# easy_eda_pro_file.net
KiCad netlist of a schematic drawn in EasyEDA Pro
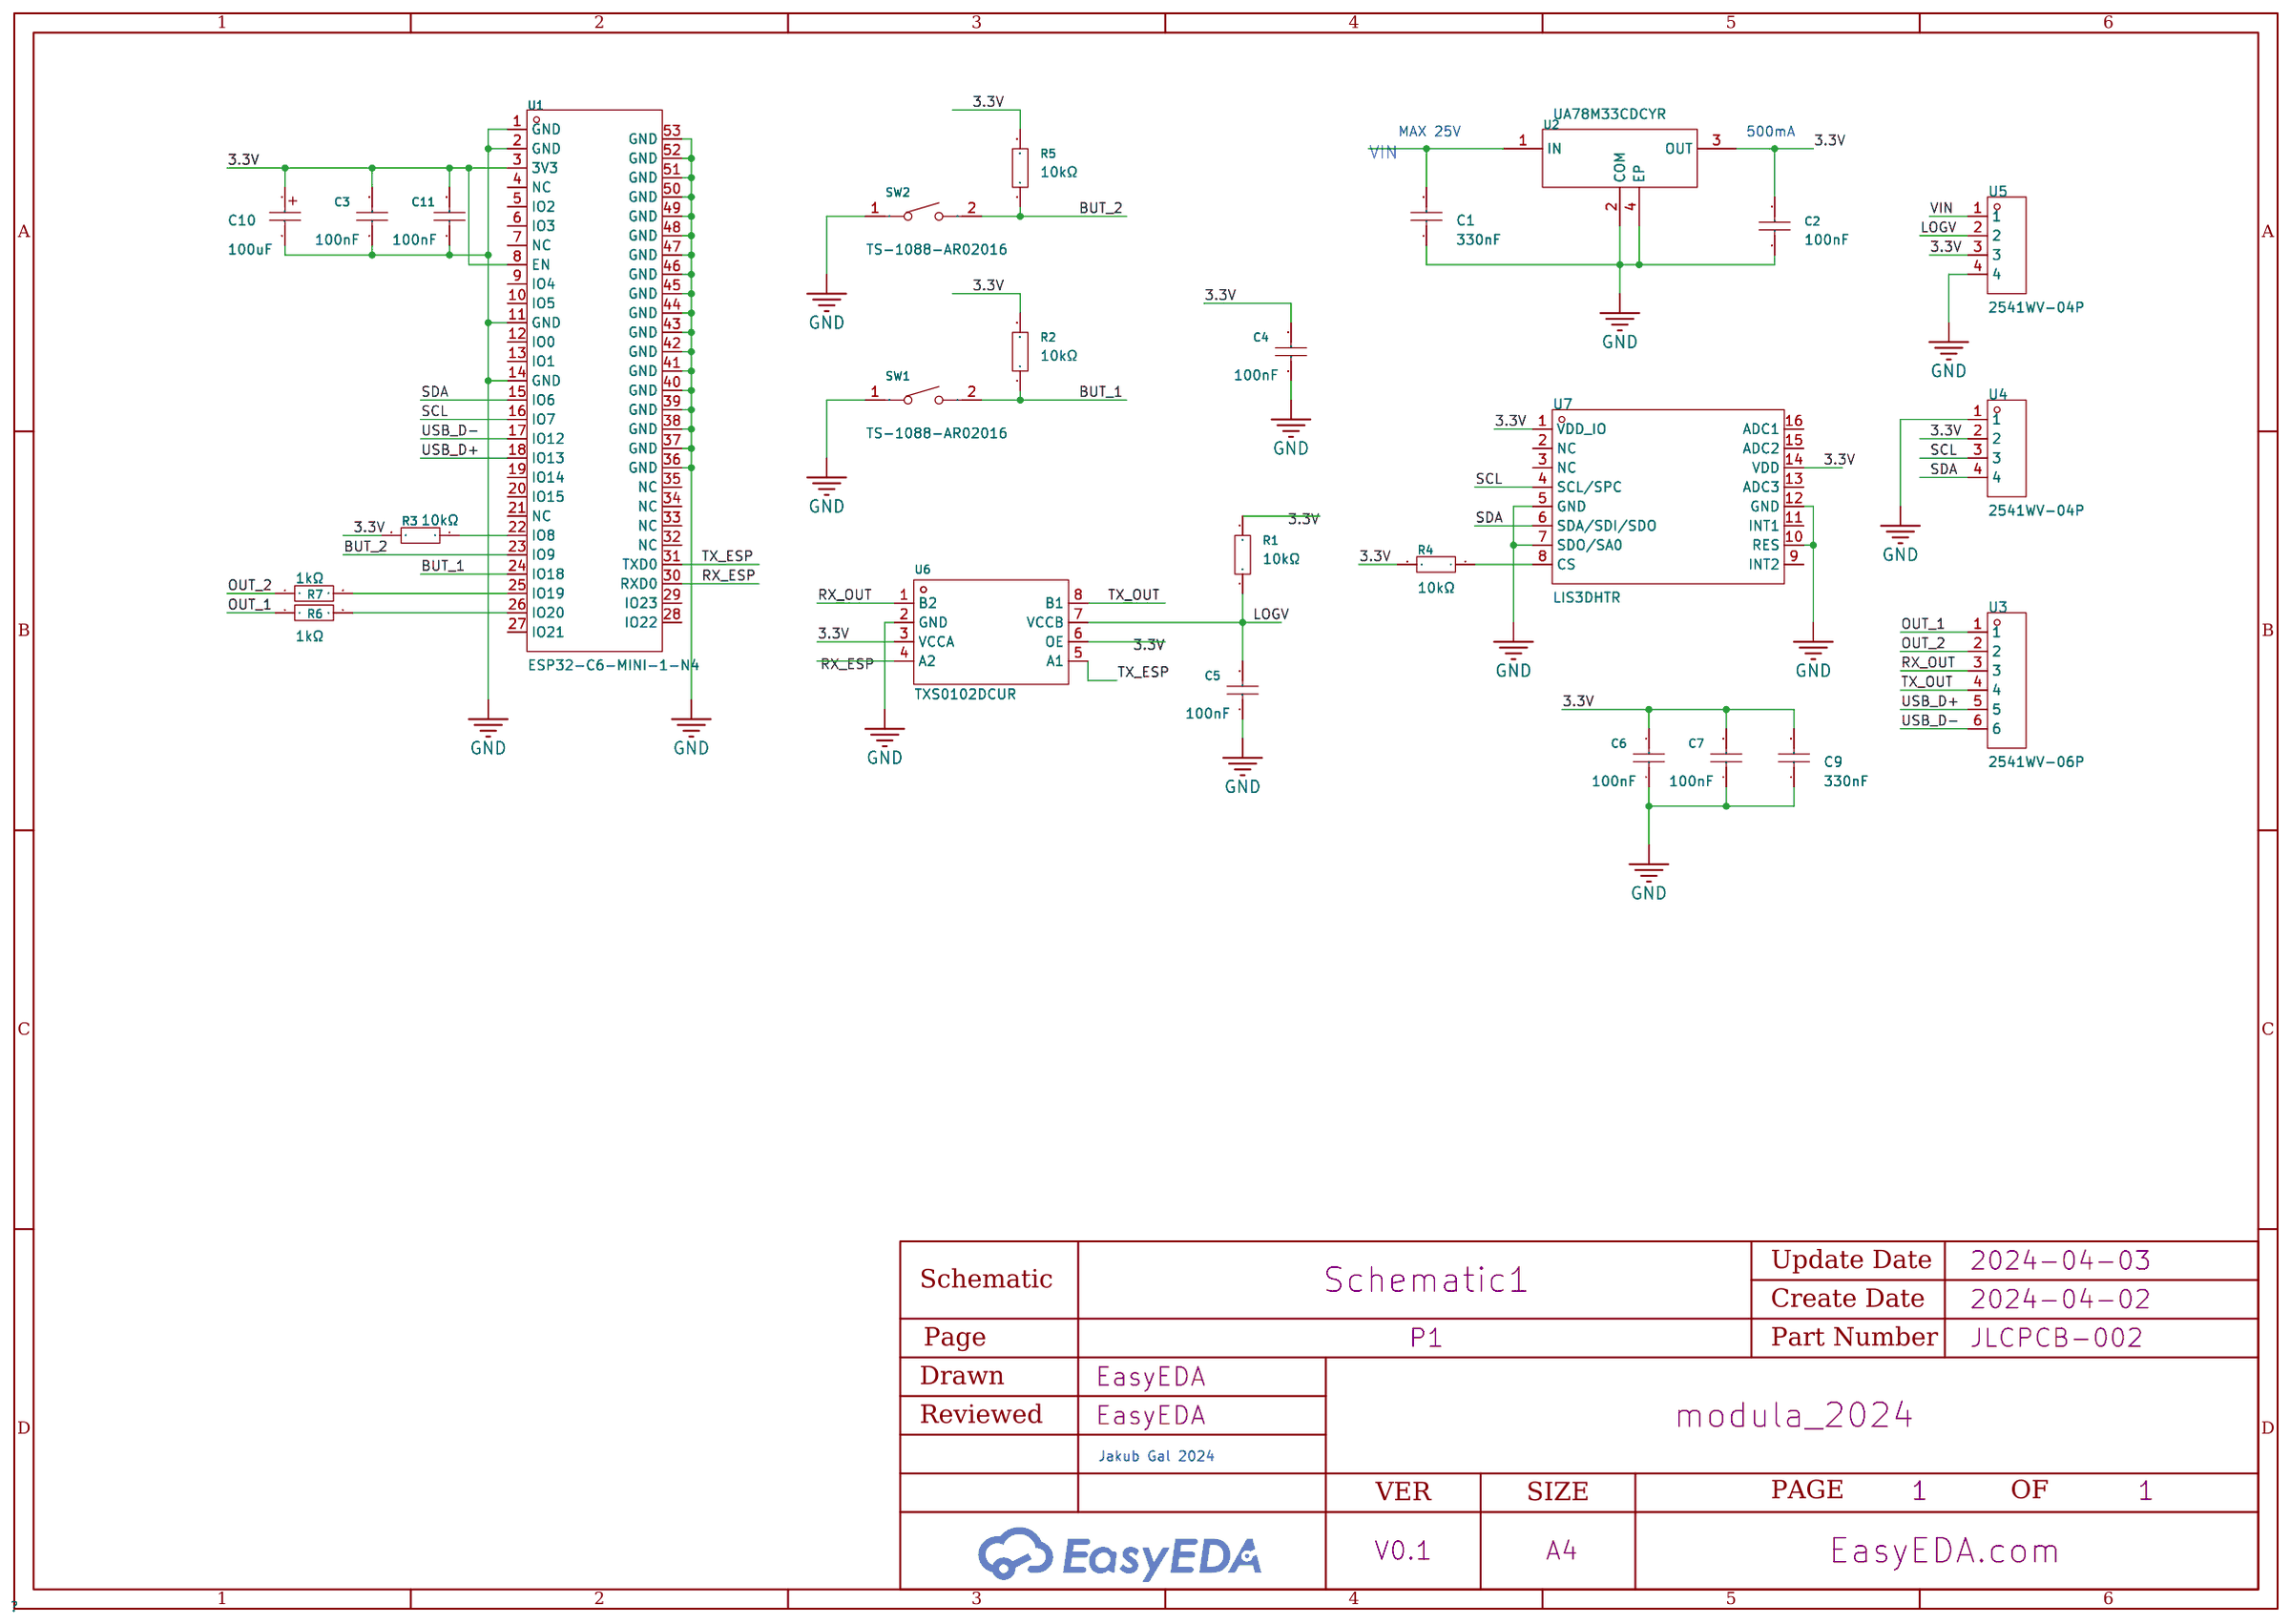
[diagram p0: schematic sheet]

(export (version "E")
  (design (tool "Eeschema 10.0.6"))
  (components
    (comp (ref "C1")
      (value "330nF")
      (footprint "easyedapro:C0805")
      (fields (field (name "Manufacturer Part") "0805B334K500NT") (field (name "Manufacturer") "FH(风华)"))
      (libsource (lib "easyedapro") (part "0805B334K500NT"))
    )
    (comp (ref "C2")
      (value "100nF")
      (footprint "easyedapro:C0603")
      (fields (field (name "Manufacturer Part") "0603B104K500NT") (field (name "Manufacturer") "FH(风华)"))
      (libsource (lib "easyedapro") (part "0603B104K500NT"))
    )
    (comp (ref "C3")
      (value "100nF")
      (footprint "easyedapro:C0603")
      (fields (field (name "Manufacturer Part") "0603B104K500NT") (field (name "Manufacturer") "FH(风华)"))
      (libsource (lib "easyedapro") (part "0603B104K500NT"))
    )
    (comp (ref "C4")
      (value "100nF")
      (footprint "easyedapro:C0603")
      (fields (field (name "Manufacturer Part") "0603B104K500NT") (field (name "Manufacturer") "FH(风华)"))
      (libsource (lib "easyedapro") (part "0603B104K500NT"))
    )
    (comp (ref "C5")
      (value "100nF")
      (footprint "easyedapro:C0603")
      (fields (field (name "Manufacturer Part") "0603B104K500NT") (field (name "Manufacturer") "FH(风华)"))
      (libsource (lib "easyedapro") (part "0603B104K500NT"))
    )
    (comp (ref "C6")
      (value "100nF")
      (footprint "easyedapro:C0603")
      (fields (field (name "Manufacturer Part") "0603B104K500NT") (field (name "Manufacturer") "FH(风华)"))
      (libsource (lib "easyedapro") (part "0603B104K500NT"))
    )
    (comp (ref "C7")
      (value "100nF")
      (footprint "easyedapro:C0603")
      (fields (field (name "Manufacturer Part") "0603B104K500NT") (field (name "Manufacturer") "FH(风华)"))
      (libsource (lib "easyedapro") (part "0603B104K500NT"))
    )
    (comp (ref "C9")
      (value "330nF")
      (footprint "easyedapro:C0805")
      (fields (field (name "Manufacturer Part") "0805B334K500NT") (field (name "Manufacturer") "FH(风华)"))
      (libsource (lib "easyedapro") (part "0805B334K500NT"))
    )
    (comp (ref "C10")
      (value "100uF")
      (footprint "easyedapro:CAP-SMD_L3.5-W2.8-R-RD")
      (fields
        (field (name "Manufacturer Part") "CA45-B-6.3V-100uF-K")
        (field (name "Manufacturer") "CEC(振华新云)")
      )
      (libsource (lib "easyedapro") (part "CA45-B-6.3V-100UF-K"))
    )
    (comp (ref "C11")
      (value "100nF")
      (footprint "easyedapro:C0603")
      (fields (field (name "Manufacturer Part") "0603B104K500NT") (field (name "Manufacturer") "FH(风华)"))
      (libsource (lib "easyedapro") (part "0603B104K500NT"))
    )
    (comp (ref "R1")
      (value "10kΩ")
      (footprint "easyedapro:R0603")
      (fields
        (field (name "Manufacturer Part") "0603WAF1002T5E")
        (field (name "Manufacturer") "UNI-ROYAL(厚声)")
      )
      (libsource (lib "easyedapro") (part "0603WAF1002T5E"))
    )
    (comp (ref "R2")
      (value "10kΩ")
      (footprint "easyedapro:R0603")
      (fields
        (field (name "Manufacturer Part") "0603WAF1002T5E")
        (field (name "Manufacturer") "UNI-ROYAL(厚声)")
      )
      (libsource (lib "easyedapro") (part "0603WAF1002T5E"))
    )
    (comp (ref "R3")
      (value "10kΩ")
      (footprint "easyedapro:R0603")
      (fields
        (field (name "Manufacturer Part") "0603WAF1002T5E")
        (field (name "Manufacturer") "UNI-ROYAL(厚声)")
      )
      (libsource (lib "easyedapro") (part "0603WAF1002T5E"))
    )
    (comp (ref "R4")
      (value "10kΩ")
      (footprint "easyedapro:R0603")
      (fields
        (field (name "Manufacturer Part") "0603WAF1002T5E")
        (field (name "Manufacturer") "UNI-ROYAL(厚声)")
      )
      (libsource (lib "easyedapro") (part "0603WAF1002T5E"))
    )
    (comp (ref "R5")
      (value "10kΩ")
      (footprint "easyedapro:R0603")
      (fields
        (field (name "Manufacturer Part") "0603WAF1002T5E")
        (field (name "Manufacturer") "UNI-ROYAL(厚声)")
      )
      (libsource (lib "easyedapro") (part "0603WAF1002T5E"))
    )
    (comp (ref "R6")
      (value "1kΩ")
      (footprint "easyedapro:R0603")
      (fields
        (field (name "Manufacturer Part") "0603WAJ0102T5E")
        (field (name "Manufacturer") "UNI-ROYAL(厚声)")
      )
      (libsource (lib "easyedapro") (part "0603WAJ0102T5E"))
    )
    (comp (ref "R7")
      (value "1kΩ")
      (footprint "easyedapro:R0603")
      (fields
        (field (name "Manufacturer Part") "0603WAJ0102T5E")
        (field (name "Manufacturer") "UNI-ROYAL(厚声)")
      )
      (libsource (lib "easyedapro") (part "0603WAJ0102T5E"))
    )
    (comp (ref "SW1")
      (value "TS-1088-AR02016")
      (footprint "easyedapro:SW-SMD_L3.9-W3.0-P4.45")
      (fields (field (name "Manufacturer") "XUNPU(讯普)"))
      (libsource (lib "easyedapro") (part "TS-1088-AR02016"))
    )
    (comp (ref "SW2")
      (value "TS-1088-AR02016")
      (footprint "easyedapro:SW-SMD_L3.9-W3.0-P4.45")
      (fields (field (name "Manufacturer") "XUNPU(讯普)"))
      (libsource (lib "easyedapro") (part "TS-1088-AR02016"))
    )
    (comp (ref "U1")
      (value "ESP32-C6-MINI-1-N4")
      (footprint "easyedapro:WIFIM-SMD_61P-L16.6-W13.2-P0.80-ESP32-C6-MINI-1-N4")
      (fields (field (name "Manufacturer") "ESPRESSIF(乐鑫)"))
      (libsource (lib "easyedapro") (part "ESP32-C6-MINI-1-N4"))
    )
    (comp (ref "U2")
      (value "UA78M33CDCYR")
      (footprint "easyedapro:SOT-223_L6.5-W3.5-P2.30-LS7.0-BR")
      (fields (field (name "Manufacturer") "TI(德州仪器)"))
      (libsource (lib "easyedapro") (part "UA78M33CDCYR"))
    )
    (comp (ref "U3")
      (value "2541WV-06P")
      (footprint "easyedapro:HDR-TH_6P-P2.54-V-M")
      (fields (field (name "Manufacturer") "HanElectricity(瀚源)"))
      (libsource (lib "easyedapro") (part "2541WV-06P"))
    )
    (comp (ref "U4")
      (value "2541WV-04P")
      (footprint "easyedapro:HDR-TH_4P-P2.54-V-M-1")
      (fields (field (name "Manufacturer") "HanElectricity(瀚源)"))
      (libsource (lib "easyedapro") (part "2541WV-04P"))
    )
    (comp (ref "U5")
      (value "2541WV-04P")
      (footprint "easyedapro:HDR-TH_4P-P2.54-V-M-1")
      (fields (field (name "Manufacturer") "HanElectricity(瀚源)"))
      (libsource (lib "easyedapro") (part "2541WV-04P"))
    )
    (comp (ref "U6")
      (value "TXS0102DCUR")
      (footprint "easyedapro:VSON8_L2.0-W2.3-P0.50-LS3.1-BL")
      (fields (field (name "Manufacturer") "TI(德州仪器)"))
      (libsource (lib "easyedapro") (part "TXS0102DCUR"))
    )
    (comp (ref "U7")
      (value "LIS3DHTR")
      (footprint "easyedapro:LGA-16_L3.0-W3.0-P0.50-TL")
      (fields (field (name "Manufacturer") "ST(意法半导体)"))
      (libsource (lib "easyedapro") (part "LIS3DHTR_C15134"))
    )
  )
  (nets
    (net (code "1") (name "/3.3V") (class "Default")
      (node (ref "C10") (pin "1") (pinfunction "1_1") (pintype "input"))
      (node (ref "C11") (pin "2") (pinfunction "2_2") (pintype "input"))
      (node (ref "C2") (pin "2") (pinfunction "2_2") (pintype "input"))
      (node (ref "C3") (pin "2") (pinfunction "2_2") (pintype "input"))
      (node (ref "C4") (pin "2") (pinfunction "2_2") (pintype "input"))
      (node (ref "C6") (pin "2") (pinfunction "2_2") (pintype "input"))
      (node (ref "C7") (pin "2") (pinfunction "2_2") (pintype "input"))
      (node (ref "C9") (pin "2") (pinfunction "2_2") (pintype "input"))
      (node (ref "R1") (pin "2") (pinfunction "2_2") (pintype "input"))
      (node (ref "R2") (pin "2") (pinfunction "2_2") (pintype "input"))
      (node (ref "R3") (pin "2") (pinfunction "2_2") (pintype "input"))
      (node (ref "R4") (pin "2") (pinfunction "2_2") (pintype "input"))
      (node (ref "R5") (pin "2") (pinfunction "2_2") (pintype "input"))
      (node (ref "U1") (pin "3") (pinfunction "3V3_3") (pintype "input"))
      (node (ref "U1") (pin "8") (pinfunction "EN_8") (pintype "input"))
      (node (ref "U2") (pin "3") (pinfunction "OUT_3") (pintype "input"))
      (node (ref "U4") (pin "2") (pinfunction "2_2") (pintype "input"))
      (node (ref "U5") (pin "3") (pinfunction "3_3") (pintype "input"))
      (node (ref "U6") (pin "3") (pinfunction "VCCA_3") (pintype "input"))
      (node (ref "U6") (pin "6") (pinfunction "OE_6") (pintype "input"))
      (node (ref "U7") (pin "1") (pinfunction "VDD_IO_1") (pintype "unspecified"))
      (node (ref "U7") (pin "14") (pinfunction "VDD_14") (pintype "unspecified"))
    )
    (net (code "2") (name "/BUT_1") (class "Default")
      (node (ref "R2") (pin "1") (pinfunction "1_1") (pintype "input"))
      (node (ref "SW1") (pin "2") (pinfunction "2_2") (pintype "input"))
      (node (ref "U1") (pin "24") (pinfunction "IO18_24") (pintype "input"))
    )
    (net (code "3") (name "/BUT_2") (class "Default")
      (node (ref "R5") (pin "1") (pinfunction "1_1") (pintype "input"))
      (node (ref "SW2") (pin "2") (pinfunction "2_2") (pintype "input"))
      (node (ref "U1") (pin "23") (pinfunction "IO9_23") (pintype "input"))
    )
    (net (code "4") (name "/LOGV") (class "Default")
      (node (ref "C5") (pin "2") (pinfunction "2_2") (pintype "input"))
      (node (ref "R1") (pin "1") (pinfunction "1_1") (pintype "input"))
      (node (ref "U5") (pin "2") (pinfunction "2_2") (pintype "input"))
      (node (ref "U6") (pin "7") (pinfunction "VCCB_7") (pintype "input"))
    )
    (net (code "5") (name "/OUT_1") (class "Default")
      (node (ref "R6") (pin "1") (pinfunction "1_1") (pintype "input"))
      (node (ref "U3") (pin "1") (pinfunction "1_1") (pintype "unspecified"))
    )
    (net (code "6") (name "/OUT_2") (class "Default")
      (node (ref "R7") (pin "1") (pinfunction "1_1") (pintype "input"))
      (node (ref "U3") (pin "2") (pinfunction "2_2") (pintype "unspecified"))
    )
    (net (code "7") (name "/RX_ESP") (class "Default")
      (node (ref "U1") (pin "30") (pinfunction "RXD0_30") (pintype "input"))
      (node (ref "U6") (pin "4") (pinfunction "A2_4") (pintype "input"))
    )
    (net (code "8") (name "/RX_OUT") (class "Default")
      (node (ref "U3") (pin "3") (pinfunction "3_3") (pintype "unspecified"))
      (node (ref "U6") (pin "1") (pinfunction "B2_1") (pintype "input"))
    )
    (net (code "9") (name "/SCL") (class "Default")
      (node (ref "U1") (pin "16") (pinfunction "IO7_16") (pintype "input"))
      (node (ref "U4") (pin "3") (pinfunction "3_3") (pintype "input"))
      (node (ref "U7") (pin "4") (pinfunction "SCL/SPC_4") (pintype "unspecified"))
    )
    (net (code "10") (name "/SDA") (class "Default")
      (node (ref "U1") (pin "15") (pinfunction "IO6_15") (pintype "input"))
      (node (ref "U4") (pin "4") (pinfunction "4_4") (pintype "input"))
      (node (ref "U7") (pin "6") (pinfunction "SDA/SDI/SDO_6") (pintype "unspecified"))
    )
    (net (code "11") (name "/TX_ESP") (class "Default")
      (node (ref "U1") (pin "31") (pinfunction "TXD0_31") (pintype "input"))
      (node (ref "U6") (pin "5") (pinfunction "A1_5") (pintype "input"))
    )
    (net (code "12") (name "/TX_OUT") (class "Default")
      (node (ref "U3") (pin "4") (pinfunction "4_4") (pintype "unspecified"))
      (node (ref "U6") (pin "8") (pinfunction "B1_8") (pintype "input"))
    )
    (net (code "13") (name "/USB_D+") (class "Default")
      (node (ref "U1") (pin "18") (pinfunction "IO13_18") (pintype "input"))
      (node (ref "U3") (pin "5") (pinfunction "5_5") (pintype "unspecified"))
    )
    (net (code "14") (name "/USB_D-") (class "Default")
      (node (ref "U1") (pin "17") (pinfunction "IO12_17") (pintype "input"))
      (node (ref "U3") (pin "6") (pinfunction "6_6") (pintype "unspecified"))
    )
    (net (code "15") (name "/VIN") (class "Default")
      (node (ref "C1") (pin "2") (pinfunction "2_2") (pintype "input"))
      (node (ref "U2") (pin "1") (pinfunction "IN_1") (pintype "input"))
      (node (ref "U5") (pin "1") (pinfunction "1_1") (pintype "input"))
    )
    (net (code "16") (name "GND") (class "Default")
      (node (ref "C1") (pin "1") (pinfunction "1_1") (pintype "input"))
      (node (ref "C10") (pin "2") (pinfunction "2_2") (pintype "input"))
      (node (ref "C11") (pin "1") (pinfunction "1_1") (pintype "input"))
      (node (ref "C2") (pin "1") (pinfunction "1_1") (pintype "input"))
      (node (ref "C3") (pin "1") (pinfunction "1_1") (pintype "input"))
      (node (ref "C4") (pin "1") (pinfunction "1_1") (pintype "input"))
      (node (ref "C5") (pin "1") (pinfunction "1_1") (pintype "input"))
      (node (ref "C6") (pin "1") (pinfunction "1_1") (pintype "input"))
      (node (ref "C7") (pin "1") (pinfunction "1_1") (pintype "input"))
      (node (ref "C9") (pin "1") (pinfunction "1_1") (pintype "input"))
      (node (ref "SW1") (pin "1") (pinfunction "1_1") (pintype "input"))
      (node (ref "SW2") (pin "1") (pinfunction "1_1") (pintype "input"))
      (node (ref "U1") (pin "1") (pinfunction "GND_1") (pintype "input"))
      (node (ref "U1") (pin "11") (pinfunction "GND_11") (pintype "input"))
      (node (ref "U1") (pin "14") (pinfunction "GND_14") (pintype "input"))
      (node (ref "U1") (pin "2") (pinfunction "GND_2") (pintype "input"))
      (node (ref "U1") (pin "36") (pinfunction "GND_36") (pintype "input"))
      (node (ref "U1") (pin "37") (pinfunction "GND_37") (pintype "input"))
      (node (ref "U1") (pin "38") (pinfunction "GND_38") (pintype "input"))
      (node (ref "U1") (pin "39") (pinfunction "GND_39") (pintype "input"))
      (node (ref "U1") (pin "40") (pinfunction "GND_40") (pintype "input"))
      (node (ref "U1") (pin "41") (pinfunction "GND_41") (pintype "input"))
      (node (ref "U1") (pin "42") (pinfunction "GND_42") (pintype "input"))
      (node (ref "U1") (pin "43") (pinfunction "GND_43") (pintype "input"))
      (node (ref "U1") (pin "44") (pinfunction "GND_44") (pintype "input"))
      (node (ref "U1") (pin "45") (pinfunction "GND_45") (pintype "input"))
      (node (ref "U1") (pin "46") (pinfunction "GND_46") (pintype "input"))
      (node (ref "U1") (pin "47") (pinfunction "GND_47") (pintype "input"))
      (node (ref "U1") (pin "48") (pinfunction "GND_48") (pintype "input"))
      (node (ref "U1") (pin "49") (pinfunction "GND_49") (pintype "input"))
      (node (ref "U1") (pin "50") (pinfunction "GND_50") (pintype "input"))
      (node (ref "U1") (pin "51") (pinfunction "GND_51") (pintype "input"))
      (node (ref "U1") (pin "52") (pinfunction "GND_52") (pintype "input"))
      (node (ref "U1") (pin "53") (pinfunction "GND_53") (pintype "input"))
      (node (ref "U2") (pin "2") (pinfunction "COM_2") (pintype "input"))
      (node (ref "U2") (pin "4") (pinfunction "EP_4") (pintype "input"))
      (node (ref "U4") (pin "1") (pinfunction "1_1") (pintype "input"))
      (node (ref "U5") (pin "4") (pinfunction "4_4") (pintype "input"))
      (node (ref "U6") (pin "2") (pinfunction "GND_2") (pintype "input"))
      (node (ref "U7") (pin "10") (pinfunction "RES_10") (pintype "unspecified"))
      (node (ref "U7") (pin "12") (pinfunction "GND_12") (pintype "unspecified"))
      (node (ref "U7") (pin "5") (pinfunction "GND_5") (pintype "unspecified"))
      (node (ref "U7") (pin "7") (pinfunction "SDO/SA0_7") (pintype "unspecified"))
    )
    (net (code "17") (name "Net-(U1-IO8)") (class "Default")
      (node (ref "R3") (pin "1") (pinfunction "1_1") (pintype "input"))
      (node (ref "U1") (pin "22") (pinfunction "IO8_22") (pintype "input"))
    )
    (net (code "18") (name "Net-(U1-IO19)") (class "Default")
      (node (ref "R7") (pin "2") (pinfunction "2_2") (pintype "input"))
      (node (ref "U1") (pin "25") (pinfunction "IO19_25") (pintype "input"))
    )
    (net (code "19") (name "Net-(U1-IO20)") (class "Default")
      (node (ref "R6") (pin "2") (pinfunction "2_2") (pintype "input"))
      (node (ref "U1") (pin "26") (pinfunction "IO20_26") (pintype "input"))
    )
    (net (code "20") (name "Net-(U7-CS)") (class "Default")
      (node (ref "R4") (pin "1") (pinfunction "1_1") (pintype "input"))
      (node (ref "U7") (pin "8") (pinfunction "CS_8") (pintype "unspecified"))
    )
    (net (code "21") (name "unconnected-(U1-IO0-Pad12)") (class "Default")
      (node (ref "U1") (pin "12") (pinfunction "IO0_12") (pintype "input"))
    )
    (net (code "22") (name "unconnected-(U1-IO1-Pad13)") (class "Default")
      (node (ref "U1") (pin "13") (pinfunction "IO1_13") (pintype "input"))
    )
    (net (code "23") (name "unconnected-(U1-IO2-Pad5)") (class "Default")
      (node (ref "U1") (pin "5") (pinfunction "IO2_5") (pintype "input"))
    )
    (net (code "24") (name "unconnected-(U1-IO3-Pad6)") (class "Default")
      (node (ref "U1") (pin "6") (pinfunction "IO3_6") (pintype "input"))
    )
    (net (code "25") (name "unconnected-(U1-IO4-Pad9)") (class "Default")
      (node (ref "U1") (pin "9") (pinfunction "IO4_9") (pintype "input"))
    )
    (net (code "26") (name "unconnected-(U1-IO5-Pad10)") (class "Default")
      (node (ref "U1") (pin "10") (pinfunction "IO5_10") (pintype "input"))
    )
    (net (code "27") (name "unconnected-(U1-IO14-Pad19)") (class "Default")
      (node (ref "U1") (pin "19") (pinfunction "IO14_19") (pintype "input"))
    )
    (net (code "28") (name "unconnected-(U1-IO15-Pad20)") (class "Default")
      (node (ref "U1") (pin "20") (pinfunction "IO15_20") (pintype "input"))
    )
    (net (code "29") (name "unconnected-(U1-IO21-Pad27)") (class "Default")
      (node (ref "U1") (pin "27") (pinfunction "IO21_27") (pintype "input"))
    )
    (net (code "30") (name "unconnected-(U1-IO22-Pad28)") (class "Default")
      (node (ref "U1") (pin "28") (pinfunction "IO22_28") (pintype "input"))
    )
    (net (code "31") (name "unconnected-(U1-IO23-Pad29)") (class "Default")
      (node (ref "U1") (pin "29") (pinfunction "IO23_29") (pintype "input"))
    )
    (net (code "32") (name "unconnected-(U1-NC-Pad4)") (class "Default")
      (node (ref "U1") (pin "4") (pinfunction "NC_4") (pintype "input"))
    )
    (net (code "33") (name "unconnected-(U1-NC-Pad7)") (class "Default")
      (node (ref "U1") (pin "7") (pinfunction "NC_7") (pintype "input"))
    )
    (net (code "34") (name "unconnected-(U1-NC-Pad21)") (class "Default")
      (node (ref "U1") (pin "21") (pinfunction "NC_21") (pintype "input"))
    )
    (net (code "35") (name "unconnected-(U1-NC-Pad32)") (class "Default")
      (node (ref "U1") (pin "32") (pinfunction "NC_32") (pintype "input"))
    )
    (net (code "36") (name "unconnected-(U1-NC-Pad33)") (class "Default")
      (node (ref "U1") (pin "33") (pinfunction "NC_33") (pintype "input"))
    )
    (net (code "37") (name "unconnected-(U1-NC-Pad34)") (class "Default")
      (node (ref "U1") (pin "34") (pinfunction "NC_34") (pintype "input"))
    )
    (net (code "38") (name "unconnected-(U1-NC-Pad35)") (class "Default")
      (node (ref "U1") (pin "35") (pinfunction "NC_35") (pintype "input"))
    )
    (net (code "39") (name "unconnected-(U7-ADC1-Pad16)") (class "Default")
      (node (ref "U7") (pin "16") (pinfunction "ADC1_16") (pintype "unspecified"))
    )
    (net (code "40") (name "unconnected-(U7-ADC2-Pad15)") (class "Default")
      (node (ref "U7") (pin "15") (pinfunction "ADC2_15") (pintype "unspecified"))
    )
    (net (code "41") (name "unconnected-(U7-ADC3-Pad13)") (class "Default")
      (node (ref "U7") (pin "13") (pinfunction "ADC3_13") (pintype "unspecified"))
    )
    (net (code "42") (name "unconnected-(U7-INT1-Pad11)") (class "Default")
      (node (ref "U7") (pin "11") (pinfunction "INT1_11") (pintype "unspecified"))
    )
    (net (code "43") (name "unconnected-(U7-INT2-Pad9)") (class "Default")
      (node (ref "U7") (pin "9") (pinfunction "INT2_9") (pintype "unspecified"))
    )
    (net (code "44") (name "unconnected-(U7-NC-Pad2)") (class "Default")
      (node (ref "U7") (pin "2") (pinfunction "NC_2") (pintype "unspecified"))
    )
    (net (code "45") (name "unconnected-(U7-NC-Pad3)") (class "Default")
      (node (ref "U7") (pin "3") (pinfunction "NC_3") (pintype "unspecified"))
    )
  )
)
